# can-weichendecoder-magnet_0_1.net
KiCad netlist of a schematic drawn in EAGLE
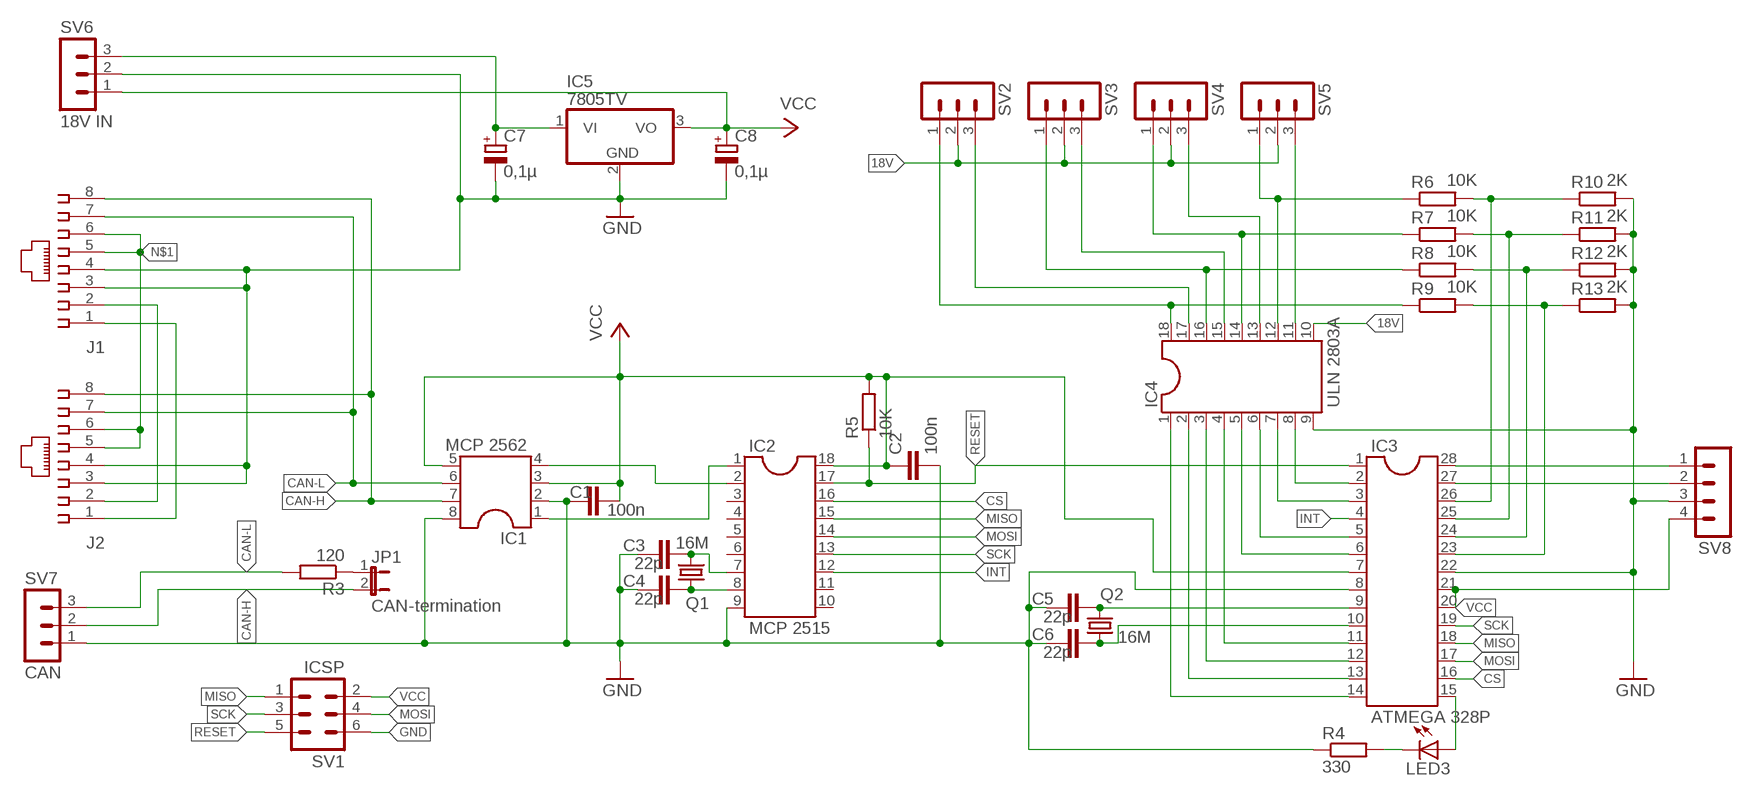
[diagram p0: schematic, sheet 1]

(export (version "E")
  (design (tool "Eeschema 10.0.6"))
  (components
    (comp (ref "C1")
      (value "100n")
      (footprint "eagle-import:C2.5-2")
      (libsource (lib "eagle-import") (part "C2.5/2"))
    )
    (comp (ref "C2")
      (value "100n")
      (footprint "eagle-import:C2.5-2")
      (libsource (lib "eagle-import") (part "C2.5/2"))
    )
    (comp (ref "C3")
      (value "22p")
      (footprint "eagle-import:C2.5-2")
      (libsource (lib "eagle-import") (part "C2.5/2"))
    )
    (comp (ref "C4")
      (value "22p")
      (footprint "eagle-import:C2.5-2")
      (libsource (lib "eagle-import") (part "C2.5/2"))
    )
    (comp (ref "C5")
      (value "22p")
      (footprint "eagle-import:C2.5-2")
      (libsource (lib "eagle-import") (part "C2.5/2"))
    )
    (comp (ref "C6")
      (value "22p")
      (footprint "eagle-import:C2.5-2")
      (libsource (lib "eagle-import") (part "C2.5/2"))
    )
    (comp (ref "C7")
      (value "0,1µ")
      (footprint "eagle-import:E2,5-6")
      (libsource (lib "eagle-import") (part "CPOL-EUE2.5-6"))
    )
    (comp (ref "C8")
      (value "0,1µ")
      (footprint "eagle-import:E2,5-6")
      (libsource (lib "eagle-import") (part "CPOL-EUE2.5-6"))
    )
    (comp (ref "IC1")
      (value "MCP 2562")
      (footprint "eagle-import:SOCKET-08")
      (libsource (lib "eagle-import") (part "DIL8S"))
    )
    (comp (ref "IC2")
      (value "MCP 2515")
      (footprint "eagle-import:SOCKET-18")
      (libsource (lib "eagle-import") (part "DIL18S"))
    )
    (comp (ref "IC3")
      (value "ATMEGA 328P")
      (footprint "eagle-import:DIL28-3")
      (libsource (lib "eagle-import") (part "DIL28-3"))
    )
    (comp (ref "IC4")
      (value "ULN 2803A")
      (footprint "eagle-import:SOCKET-18")
      (libsource (lib "eagle-import") (part "DIL18S"))
    )
    (comp (ref "IC5")
      (value "7805TV")
      (footprint "eagle-import:TO220V")
      (libsource (lib "eagle-import") (part "78TV05"))
    )
    (comp (ref "J1")
      (value "215877-7")
      (footprint "eagle-import:215877-7")
      (libsource (lib "eagle-import") (part "215877-7"))
    )
    (comp (ref "J2")
      (value "215877-7")
      (footprint "eagle-import:215877-7")
      (libsource (lib "eagle-import") (part "215877-7"))
    )
    (comp (ref "JP1")
      (value "CAN-termination")
      (footprint "eagle-import:JP1")
      (libsource (lib "eagle-import") (part "JP1E"))
    )
    (comp (ref "LED3")
      (value "LED5MM")
      (footprint "eagle-import:LED5MM")
      (libsource (lib "eagle-import") (part "LED5MM"))
    )
    (comp (ref "Q1")
      (value "16M")
      (footprint "eagle-import:HC49_S")
      (libsource (lib "eagle-import") (part "CRYSTALHC49S"))
    )
    (comp (ref "Q2")
      (value "16M")
      (footprint "eagle-import:HC49_S")
      (libsource (lib "eagle-import") (part "CRYSTALHC49S"))
    )
    (comp (ref "R3")
      (value "120")
      (footprint "eagle-import:0207_10")
      (libsource (lib "eagle-import") (part "R-EU_0207/10"))
    )
    (comp (ref "R4")
      (value "330")
      (footprint "eagle-import:0207_10")
      (libsource (lib "eagle-import") (part "R-EU_0207/10"))
    )
    (comp (ref "R5")
      (value "10K")
      (footprint "eagle-import:0207_10")
      (libsource (lib "eagle-import") (part "R-EU_0207/10"))
    )
    (comp (ref "R6")
      (value "10K")
      (footprint "eagle-import:0207_10")
      (libsource (lib "eagle-import") (part "R-EU_0207/10"))
    )
    (comp (ref "R7")
      (value "10K")
      (footprint "eagle-import:0207_10")
      (libsource (lib "eagle-import") (part "R-EU_0207/10"))
    )
    (comp (ref "R8")
      (value "10K")
      (footprint "eagle-import:0207_10")
      (libsource (lib "eagle-import") (part "R-EU_0207/10"))
    )
    (comp (ref "R9")
      (value "10K")
      (footprint "eagle-import:0207_10")
      (libsource (lib "eagle-import") (part "R-EU_0207/10"))
    )
    (comp (ref "R10")
      (value "2K")
      (footprint "eagle-import:0207_10")
      (libsource (lib "eagle-import") (part "R-EU_0207/10"))
    )
    (comp (ref "R11")
      (value "2K")
      (footprint "eagle-import:0207_10")
      (libsource (lib "eagle-import") (part "R-EU_0207/10"))
    )
    (comp (ref "R12")
      (value "2K")
      (footprint "eagle-import:0207_10")
      (libsource (lib "eagle-import") (part "R-EU_0207/10"))
    )
    (comp (ref "R13")
      (value "2K")
      (footprint "eagle-import:0207_10")
      (libsource (lib "eagle-import") (part "R-EU_0207/10"))
    )
    (comp (ref "SV1")
      (value "ICSP")
      (footprint "eagle-import:MA03-2")
      (libsource (lib "eagle-import") (part "MA03-2"))
    )
    (comp (ref "SV2")
      (value "MA03-1")
      (footprint "eagle-import:MA03-1")
      (libsource (lib "eagle-import") (part "MA03-1"))
    )
    (comp (ref "SV3")
      (value "MA03-1")
      (footprint "eagle-import:MA03-1")
      (libsource (lib "eagle-import") (part "MA03-1"))
    )
    (comp (ref "SV4")
      (value "MA03-1")
      (footprint "eagle-import:MA03-1")
      (libsource (lib "eagle-import") (part "MA03-1"))
    )
    (comp (ref "SV5")
      (value "MA03-1")
      (footprint "eagle-import:MA03-1")
      (libsource (lib "eagle-import") (part "MA03-1"))
    )
    (comp (ref "SV6")
      (value "18V IN")
      (footprint "eagle-import:MA03-1")
      (libsource (lib "eagle-import") (part "MA03-1"))
    )
    (comp (ref "SV7")
      (value "CAN")
      (footprint "eagle-import:MA03-1")
      (libsource (lib "eagle-import") (part "MA03-1"))
    )
    (comp (ref "SV8")
      (value "MA04-1")
      (footprint "eagle-import:MA04-1")
      (libsource (lib "eagle-import") (part "MA04-1"))
    )
  )
  (nets
    (net (code "1") (name "18V") (class "Default")
      (node (ref "C7") (pin "+") (pinfunction "+_+") (pintype "passive"))
      (node (ref "IC4") (pin "10") (pinfunction "10_10") (pintype "passive"))
      (node (ref "IC5") (pin "1") (pinfunction "VI_1") (pintype "input"))
      (node (ref "SV2") (pin "2") (pinfunction "2_2") (pintype "passive"))
      (node (ref "SV3") (pin "2") (pinfunction "2_2") (pintype "passive"))
      (node (ref "SV4") (pin "2") (pinfunction "2_2") (pintype "passive"))
      (node (ref "SV5") (pin "2") (pinfunction "2_2") (pintype "passive"))
      (node (ref "SV6") (pin "3") (pinfunction "3_3") (pintype "passive"))
    )
    (net (code "2") (name "CAN-H") (class "Default")
      (node (ref "IC1") (pin "7") (pinfunction "7_7") (pintype "passive"))
      (node (ref "J1") (pin "8") (pinfunction "8_8") (pintype "passive"))
      (node (ref "J2") (pin "8") (pinfunction "8_8") (pintype "passive"))
      (node (ref "JP1") (pin "2") (pinfunction "2_2") (pintype "passive"))
      (node (ref "SV7") (pin "2") (pinfunction "2_2") (pintype "passive"))
    )
    (net (code "3") (name "CAN-L") (class "Default")
      (node (ref "IC1") (pin "6") (pinfunction "6_6") (pintype "passive"))
      (node (ref "J1") (pin "7") (pinfunction "7_7") (pintype "passive"))
      (node (ref "J2") (pin "7") (pinfunction "7_7") (pintype "passive"))
      (node (ref "R3") (pin "2") (pinfunction "2_2") (pintype "passive"))
      (node (ref "SV7") (pin "3") (pinfunction "3_3") (pintype "passive"))
    )
    (net (code "4") (name "CS") (class "Default")
      (node (ref "IC2") (pin "16") (pinfunction "16_16") (pintype "passive"))
      (node (ref "IC3") (pin "16") (pinfunction "16_16") (pintype "passive"))
    )
    (net (code "5") (name "GND") (class "Default")
      (node (ref "C1") (pin "1") (pinfunction "1_1") (pintype "passive"))
      (node (ref "C2") (pin "2") (pinfunction "2_2") (pintype "passive"))
      (node (ref "C3") (pin "1") (pinfunction "1_1") (pintype "passive"))
      (node (ref "C4") (pin "1") (pinfunction "1_1") (pintype "passive"))
      (node (ref "C5") (pin "1") (pinfunction "1_1") (pintype "passive"))
      (node (ref "C6") (pin "1") (pinfunction "1_1") (pintype "passive"))
      (node (ref "C7") (pin "-") (pinfunction "-_-") (pintype "passive"))
      (node (ref "C8") (pin "-") (pinfunction "-_-") (pintype "passive"))
      (node (ref "IC1") (pin "2") (pinfunction "2_2") (pintype "passive"))
      (node (ref "IC1") (pin "8") (pinfunction "8_8") (pintype "passive"))
      (node (ref "IC2") (pin "9") (pinfunction "9_9") (pintype "passive"))
      (node (ref "IC3") (pin "22") (pinfunction "22_22") (pintype "passive"))
      (node (ref "IC3") (pin "8") (pinfunction "8_8") (pintype "passive"))
      (node (ref "IC4") (pin "9") (pinfunction "9_9") (pintype "passive"))
      (node (ref "IC5") (pin "2") (pinfunction "GND_2") (pintype "passive"))
      (node (ref "J1") (pin "3") (pinfunction "3_3") (pintype "passive"))
      (node (ref "J1") (pin "4") (pinfunction "4_4") (pintype "passive"))
      (node (ref "J2") (pin "3") (pinfunction "3_3") (pintype "passive"))
      (node (ref "J2") (pin "4") (pinfunction "4_4") (pintype "passive"))
      (node (ref "R10") (pin "2") (pinfunction "2_2") (pintype "passive"))
      (node (ref "R11") (pin "2") (pinfunction "2_2") (pintype "passive"))
      (node (ref "R12") (pin "2") (pinfunction "2_2") (pintype "passive"))
      (node (ref "R13") (pin "2") (pinfunction "2_2") (pintype "passive"))
      (node (ref "R4") (pin "1") (pinfunction "1_1") (pintype "passive"))
      (node (ref "SV1") (pin "6") (pinfunction "6_6") (pintype "passive"))
      (node (ref "SV6") (pin "2") (pinfunction "2_2") (pintype "passive"))
      (node (ref "SV7") (pin "1") (pinfunction "1_1") (pintype "passive"))
      (node (ref "SV8") (pin "3") (pinfunction "3_3") (pintype "passive"))
    )
    (net (code "6") (name "INT") (class "Default")
      (node (ref "IC2") (pin "12") (pinfunction "12_12") (pintype "passive"))
      (node (ref "IC3") (pin "4") (pinfunction "4_4") (pintype "passive"))
    )
    (net (code "7") (name "MISO") (class "Default")
      (node (ref "IC2") (pin "15") (pinfunction "15_15") (pintype "passive"))
      (node (ref "IC3") (pin "18") (pinfunction "18_18") (pintype "passive"))
      (node (ref "SV1") (pin "1") (pinfunction "1_1") (pintype "passive"))
    )
    (net (code "8") (name "MOSI") (class "Default")
      (node (ref "IC2") (pin "14") (pinfunction "14_14") (pintype "passive"))
      (node (ref "IC3") (pin "17") (pinfunction "17_17") (pintype "passive"))
      (node (ref "SV1") (pin "4") (pinfunction "4_4") (pintype "passive"))
    )
    (net (code "9") (name "N$1") (class "Default")
      (node (ref "J1") (pin "5") (pinfunction "5_5") (pintype "passive"))
      (node (ref "J1") (pin "6") (pinfunction "6_6") (pintype "passive"))
      (node (ref "J2") (pin "5") (pinfunction "5_5") (pintype "passive"))
      (node (ref "J2") (pin "6") (pinfunction "6_6") (pintype "passive"))
    )
    (net (code "10") (name "Net-(C3-Pad2)") (class "Default")
      (node (ref "C3") (pin "2") (pinfunction "2_2") (pintype "passive"))
      (node (ref "IC2") (pin "7") (pinfunction "7_7") (pintype "passive"))
      (node (ref "Q1") (pin "2") (pinfunction "2_2") (pintype "passive"))
    )
    (net (code "11") (name "Net-(C4-Pad2)") (class "Default")
      (node (ref "C4") (pin "2") (pinfunction "2_2") (pintype "passive"))
      (node (ref "IC2") (pin "8") (pinfunction "8_8") (pintype "passive"))
      (node (ref "Q1") (pin "1") (pinfunction "1_1") (pintype "passive"))
    )
    (net (code "12") (name "Net-(C5-Pad2)") (class "Default")
      (node (ref "C5") (pin "2") (pinfunction "2_2") (pintype "passive"))
      (node (ref "IC3") (pin "9") (pinfunction "9_9") (pintype "passive"))
      (node (ref "Q2") (pin "2") (pinfunction "2_2") (pintype "passive"))
    )
    (net (code "13") (name "Net-(C6-Pad2)") (class "Default")
      (node (ref "C6") (pin "2") (pinfunction "2_2") (pintype "passive"))
      (node (ref "IC3") (pin "10") (pinfunction "10_10") (pintype "passive"))
      (node (ref "Q2") (pin "1") (pinfunction "1_1") (pintype "passive"))
    )
    (net (code "14") (name "Net-(IC1-Pad1)") (class "Default")
      (node (ref "IC1") (pin "1") (pinfunction "1_1") (pintype "passive"))
      (node (ref "IC2") (pin "1") (pinfunction "1_1") (pintype "passive"))
    )
    (net (code "15") (name "Net-(IC1-Pad4)") (class "Default")
      (node (ref "IC1") (pin "4") (pinfunction "4_4") (pintype "passive"))
      (node (ref "IC2") (pin "2") (pinfunction "2_2") (pintype "passive"))
    )
    (net (code "16") (name "Net-(IC3-Pad2)") (class "Default")
      (node (ref "IC3") (pin "2") (pinfunction "2_2") (pintype "passive"))
      (node (ref "IC4") (pin "8") (pinfunction "8_8") (pintype "passive"))
    )
    (net (code "17") (name "Net-(IC3-Pad3)") (class "Default")
      (node (ref "IC3") (pin "3") (pinfunction "3_3") (pintype "passive"))
      (node (ref "IC4") (pin "7") (pinfunction "7_7") (pintype "passive"))
    )
    (net (code "18") (name "Net-(IC3-Pad5)") (class "Default")
      (node (ref "IC3") (pin "5") (pinfunction "5_5") (pintype "passive"))
      (node (ref "IC4") (pin "6") (pinfunction "6_6") (pintype "passive"))
    )
    (net (code "19") (name "Net-(IC3-Pad6)") (class "Default")
      (node (ref "IC3") (pin "6") (pinfunction "6_6") (pintype "passive"))
      (node (ref "IC4") (pin "5") (pinfunction "5_5") (pintype "passive"))
    )
    (net (code "20") (name "Net-(IC3-Pad11)") (class "Default")
      (node (ref "IC3") (pin "11") (pinfunction "11_11") (pintype "passive"))
      (node (ref "IC4") (pin "4") (pinfunction "4_4") (pintype "passive"))
    )
    (net (code "21") (name "Net-(IC3-Pad12)") (class "Default")
      (node (ref "IC3") (pin "12") (pinfunction "12_12") (pintype "passive"))
      (node (ref "IC4") (pin "3") (pinfunction "3_3") (pintype "passive"))
    )
    (net (code "22") (name "Net-(IC3-Pad13)") (class "Default")
      (node (ref "IC3") (pin "13") (pinfunction "13_13") (pintype "passive"))
      (node (ref "IC4") (pin "2") (pinfunction "2_2") (pintype "passive"))
    )
    (net (code "23") (name "Net-(IC3-Pad14)") (class "Default")
      (node (ref "IC3") (pin "14") (pinfunction "14_14") (pintype "passive"))
      (node (ref "IC4") (pin "1") (pinfunction "1_1") (pintype "passive"))
    )
    (net (code "24") (name "Net-(IC3-Pad15)") (class "Default")
      (node (ref "IC3") (pin "15") (pinfunction "15_15") (pintype "passive"))
      (node (ref "LED3") (pin "A") (pinfunction "A_A") (pintype "passive"))
    )
    (net (code "25") (name "Net-(IC3-Pad23)") (class "Default")
      (node (ref "IC3") (pin "23") (pinfunction "23_23") (pintype "passive"))
      (node (ref "R13") (pin "1") (pinfunction "1_1") (pintype "passive"))
      (node (ref "R9") (pin "2") (pinfunction "2_2") (pintype "passive"))
    )
    (net (code "26") (name "Net-(IC3-Pad24)") (class "Default")
      (node (ref "IC3") (pin "24") (pinfunction "24_24") (pintype "passive"))
      (node (ref "R12") (pin "1") (pinfunction "1_1") (pintype "passive"))
      (node (ref "R8") (pin "2") (pinfunction "2_2") (pintype "passive"))
    )
    (net (code "27") (name "Net-(IC3-Pad25)") (class "Default")
      (node (ref "IC3") (pin "25") (pinfunction "25_25") (pintype "passive"))
      (node (ref "R11") (pin "1") (pinfunction "1_1") (pintype "passive"))
      (node (ref "R7") (pin "2") (pinfunction "2_2") (pintype "passive"))
    )
    (net (code "28") (name "Net-(IC3-Pad26)") (class "Default")
      (node (ref "IC3") (pin "26") (pinfunction "26_26") (pintype "passive"))
      (node (ref "R10") (pin "1") (pinfunction "1_1") (pintype "passive"))
      (node (ref "R6") (pin "2") (pinfunction "2_2") (pintype "passive"))
    )
    (net (code "29") (name "Net-(IC3-Pad27)") (class "Default")
      (node (ref "IC3") (pin "27") (pinfunction "27_27") (pintype "passive"))
      (node (ref "SV8") (pin "2") (pinfunction "2_2") (pintype "passive"))
    )
    (net (code "30") (name "Net-(IC3-Pad28)") (class "Default")
      (node (ref "IC3") (pin "28") (pinfunction "28_28") (pintype "passive"))
      (node (ref "SV8") (pin "1") (pinfunction "1_1") (pintype "passive"))
    )
    (net (code "31") (name "Net-(IC4-Pad11)") (class "Default")
      (node (ref "IC4") (pin "11") (pinfunction "11_11") (pintype "passive"))
      (node (ref "SV5") (pin "3") (pinfunction "3_3") (pintype "passive"))
    )
    (net (code "32") (name "Net-(IC4-Pad12)") (class "Default")
      (node (ref "IC4") (pin "12") (pinfunction "12_12") (pintype "passive"))
      (node (ref "R6") (pin "1") (pinfunction "1_1") (pintype "passive"))
      (node (ref "SV5") (pin "1") (pinfunction "1_1") (pintype "passive"))
    )
    (net (code "33") (name "Net-(IC4-Pad13)") (class "Default")
      (node (ref "IC4") (pin "13") (pinfunction "13_13") (pintype "passive"))
      (node (ref "SV4") (pin "3") (pinfunction "3_3") (pintype "passive"))
    )
    (net (code "34") (name "Net-(IC4-Pad14)") (class "Default")
      (node (ref "IC4") (pin "14") (pinfunction "14_14") (pintype "passive"))
      (node (ref "R7") (pin "1") (pinfunction "1_1") (pintype "passive"))
      (node (ref "SV4") (pin "1") (pinfunction "1_1") (pintype "passive"))
    )
    (net (code "35") (name "Net-(IC4-Pad15)") (class "Default")
      (node (ref "IC4") (pin "15") (pinfunction "15_15") (pintype "passive"))
      (node (ref "SV3") (pin "3") (pinfunction "3_3") (pintype "passive"))
    )
    (net (code "36") (name "Net-(IC4-Pad16)") (class "Default")
      (node (ref "IC4") (pin "16") (pinfunction "16_16") (pintype "passive"))
      (node (ref "R8") (pin "1") (pinfunction "1_1") (pintype "passive"))
      (node (ref "SV3") (pin "1") (pinfunction "1_1") (pintype "passive"))
    )
    (net (code "37") (name "Net-(IC4-Pad17)") (class "Default")
      (node (ref "IC4") (pin "17") (pinfunction "17_17") (pintype "passive"))
      (node (ref "SV2") (pin "3") (pinfunction "3_3") (pintype "passive"))
    )
    (net (code "38") (name "Net-(IC4-Pad18)") (class "Default")
      (node (ref "IC4") (pin "18") (pinfunction "18_18") (pintype "passive"))
      (node (ref "R9") (pin "1") (pinfunction "1_1") (pintype "passive"))
      (node (ref "SV2") (pin "1") (pinfunction "1_1") (pintype "passive"))
    )
    (net (code "39") (name "Net-(J1-Pad1)") (class "Default")
      (node (ref "J1") (pin "1") (pinfunction "1_1") (pintype "passive"))
      (node (ref "J2") (pin "1") (pinfunction "1_1") (pintype "passive"))
    )
    (net (code "40") (name "Net-(J1-Pad2)") (class "Default")
      (node (ref "J1") (pin "2") (pinfunction "2_2") (pintype "passive"))
      (node (ref "J2") (pin "2") (pinfunction "2_2") (pintype "passive"))
    )
    (net (code "41") (name "Net-(JP1-Pad1)") (class "Default")
      (node (ref "JP1") (pin "1") (pinfunction "1_1") (pintype "passive"))
      (node (ref "R3") (pin "1") (pinfunction "1_1") (pintype "passive"))
    )
    (net (code "42") (name "Net-(LED3-C)") (class "Default")
      (node (ref "LED3") (pin "K") (pinfunction "C_K") (pintype "passive"))
      (node (ref "R4") (pin "2") (pinfunction "2_2") (pintype "passive"))
    )
    (net (code "43") (name "RESET") (class "Default")
      (node (ref "IC2") (pin "17") (pinfunction "17_17") (pintype "passive"))
      (node (ref "IC3") (pin "1") (pinfunction "1_1") (pintype "passive"))
      (node (ref "R5") (pin "1") (pinfunction "1_1") (pintype "passive"))
      (node (ref "SV1") (pin "5") (pinfunction "5_5") (pintype "passive"))
    )
    (net (code "44") (name "SCK") (class "Default")
      (node (ref "IC2") (pin "13") (pinfunction "13_13") (pintype "passive"))
      (node (ref "IC3") (pin "19") (pinfunction "19_19") (pintype "passive"))
      (node (ref "SV1") (pin "3") (pinfunction "3_3") (pintype "passive"))
    )
    (net (code "45") (name "VCC") (class "Default")
      (node (ref "C1") (pin "2") (pinfunction "2_2") (pintype "passive"))
      (node (ref "C2") (pin "1") (pinfunction "1_1") (pintype "passive"))
      (node (ref "C8") (pin "+") (pinfunction "+_+") (pintype "passive"))
      (node (ref "IC1") (pin "3") (pinfunction "3_3") (pintype "passive"))
      (node (ref "IC1") (pin "5") (pinfunction "5_5") (pintype "passive"))
      (node (ref "IC2") (pin "18") (pinfunction "18_18") (pintype "passive"))
      (node (ref "IC3") (pin "20") (pinfunction "20_20") (pintype "passive"))
      (node (ref "IC3") (pin "21") (pinfunction "21_21") (pintype "passive"))
      (node (ref "IC3") (pin "7") (pinfunction "7_7") (pintype "passive"))
      (node (ref "IC5") (pin "3") (pinfunction "VO_3") (pintype "passive"))
      (node (ref "R5") (pin "2") (pinfunction "2_2") (pintype "passive"))
      (node (ref "SV1") (pin "2") (pinfunction "2_2") (pintype "passive"))
      (node (ref "SV6") (pin "1") (pinfunction "1_1") (pintype "passive"))
      (node (ref "SV8") (pin "4") (pinfunction "4_4") (pintype "passive"))
    )
    (net (code "46") (name "unconnected-(IC2-Pad3)") (class "Default")
      (node (ref "IC2") (pin "3") (pinfunction "3_3") (pintype "passive"))
    )
    (net (code "47") (name "unconnected-(IC2-Pad4)") (class "Default")
      (node (ref "IC2") (pin "4") (pinfunction "4_4") (pintype "passive"))
    )
    (net (code "48") (name "unconnected-(IC2-Pad5)") (class "Default")
      (node (ref "IC2") (pin "5") (pinfunction "5_5") (pintype "passive"))
    )
    (net (code "49") (name "unconnected-(IC2-Pad6)") (class "Default")
      (node (ref "IC2") (pin "6") (pinfunction "6_6") (pintype "passive"))
    )
    (net (code "50") (name "unconnected-(IC2-Pad10)") (class "Default")
      (node (ref "IC2") (pin "10") (pinfunction "10_10") (pintype "passive"))
    )
    (net (code "51") (name "unconnected-(IC2-Pad11)") (class "Default")
      (node (ref "IC2") (pin "11") (pinfunction "11_11") (pintype "passive"))
    )
  )
)
